# touch_555.net
KiCad netlist of a schematic drawn in EAGLE
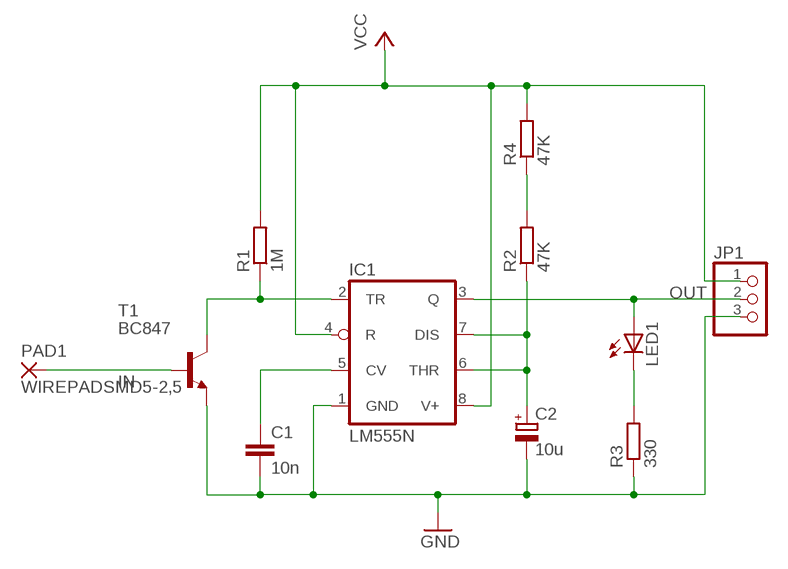
[diagram p0: schematic, sheet 1]

(export (version "E")
  (design (tool "Eeschema 10.0.6"))
  (components
    (comp (ref "C1")
      (value "10n")
      (footprint "eagle-import:C0805")
      (libsource (lib "eagle-import") (part "C-EUC0805"))
    )
    (comp (ref "C2")
      (value "10u")
      (footprint "eagle-import:E2,5-6")
      (libsource (lib "eagle-import") (part "CPOL-EUE2.5-6"))
    )
    (comp (ref "IC1")
      (value "LM555N")
      (footprint "eagle-import:DIL08")
      (libsource (lib "eagle-import") (part "555NLM"))
    )
    (comp (ref "JP1")
      (value "PINHD-1X3")
      (footprint "eagle-import:1X03")
      (libsource (lib "eagle-import") (part "PINHD-1X3"))
    )
    (comp (ref "LED1")
      (value "LEDCHIPLED_1206")
      (footprint "eagle-import:CHIPLED_1206")
      (libsource (lib "eagle-import") (part "LEDCHIPLED_1206"))
    )
    (comp (ref "PAD1")
      (value "WIREPADSMD5-2,5")
      (footprint "eagle-import:5-2,5")
      (libsource (lib "eagle-import") (part "WIREPADSMD5-2,5"))
    )
    (comp (ref "R1")
      (value "1M")
      (footprint "eagle-import:R0805")
      (libsource (lib "eagle-import") (part "R-EU_R0805"))
    )
    (comp (ref "R2")
      (value "47K")
      (footprint "eagle-import:R0805")
      (libsource (lib "eagle-import") (part "R-EU_R0805"))
    )
    (comp (ref "R3")
      (value "330")
      (footprint "eagle-import:R0805")
      (libsource (lib "eagle-import") (part "R-EU_R0805"))
    )
    (comp (ref "R4")
      (value "47K")
      (footprint "eagle-import:R0805")
      (libsource (lib "eagle-import") (part "R-EU_R0805"))
    )
    (comp (ref "T1")
      (value "BC847")
      (footprint "eagle-import:SOT23")
      (libsource (lib "eagle-import") (part "BC847"))
    )
  )
  (nets
    (net (code "1") (name "/IN") (class "Default")
      (node (ref "PAD1") (pin "1") (pinfunction "P_1") (pintype "passive"))
      (node (ref "T1") (pin "1") (pinfunction "B_1") (pintype "passive"))
    )
    (net (code "2") (name "/OUT") (class "Default")
      (node (ref "IC1") (pin "3") (pinfunction "Q_3") (pintype "output"))
      (node (ref "JP1") (pin "2") (pinfunction "2_2") (pintype "passive"))
      (node (ref "LED1") (pin "A") (pinfunction "A_A") (pintype "passive"))
    )
    (net (code "3") (name "GND") (class "Default")
      (node (ref "C1") (pin "2") (pinfunction "2_2") (pintype "passive"))
      (node (ref "C2") (pin "-") (pinfunction "-_-") (pintype "passive"))
      (node (ref "IC1") (pin "1") (pinfunction "GND_1") (pintype "power_in"))
      (node (ref "JP1") (pin "3") (pinfunction "3_3") (pintype "passive"))
      (node (ref "R3") (pin "1") (pinfunction "1_1") (pintype "passive"))
      (node (ref "T1") (pin "2") (pinfunction "E_2") (pintype "passive"))
    )
    (net (code "4") (name "Net-(IC1-CV)") (class "Default")
      (node (ref "C1") (pin "1") (pinfunction "1_1") (pintype "passive"))
      (node (ref "IC1") (pin "5") (pinfunction "CV_5") (pintype "input"))
    )
    (net (code "5") (name "Net-(IC1-DIS)") (class "Default")
      (node (ref "C2") (pin "+") (pinfunction "+_+") (pintype "passive"))
      (node (ref "IC1") (pin "6") (pinfunction "THR_6") (pintype "input"))
      (node (ref "IC1") (pin "7") (pinfunction "DIS_7") (pintype "input"))
      (node (ref "R2") (pin "1") (pinfunction "1_1") (pintype "passive"))
    )
    (net (code "6") (name "Net-(IC1-TR)") (class "Default")
      (node (ref "IC1") (pin "2") (pinfunction "TR_2") (pintype "input"))
      (node (ref "R1") (pin "1") (pinfunction "1_1") (pintype "passive"))
      (node (ref "T1") (pin "3") (pinfunction "C_3") (pintype "passive"))
    )
    (net (code "7") (name "Net-(LED1-PadC)") (class "Default")
      (node (ref "LED1") (pin "C") (pinfunction "C_C") (pintype "passive"))
      (node (ref "R3") (pin "2") (pinfunction "2_2") (pintype "passive"))
    )
    (net (code "8") (name "Net-(R2-Pad2)") (class "Default")
      (node (ref "R2") (pin "2") (pinfunction "2_2") (pintype "passive"))
      (node (ref "R4") (pin "1") (pinfunction "1_1") (pintype "passive"))
    )
    (net (code "9") (name "VCC") (class "Default")
      (node (ref "IC1") (pin "4") (pinfunction "R_4") (pintype "input"))
      (node (ref "IC1") (pin "8") (pinfunction "V+_8") (pintype "power_in"))
      (node (ref "JP1") (pin "1") (pinfunction "1_1") (pintype "passive"))
      (node (ref "R1") (pin "2") (pinfunction "2_2") (pintype "passive"))
      (node (ref "R4") (pin "2") (pinfunction "2_2") (pintype "passive"))
    )
  )
)
